# DM1090FFC_Connector.net
KiCad netlist of a schematic drawn in Altium Designer
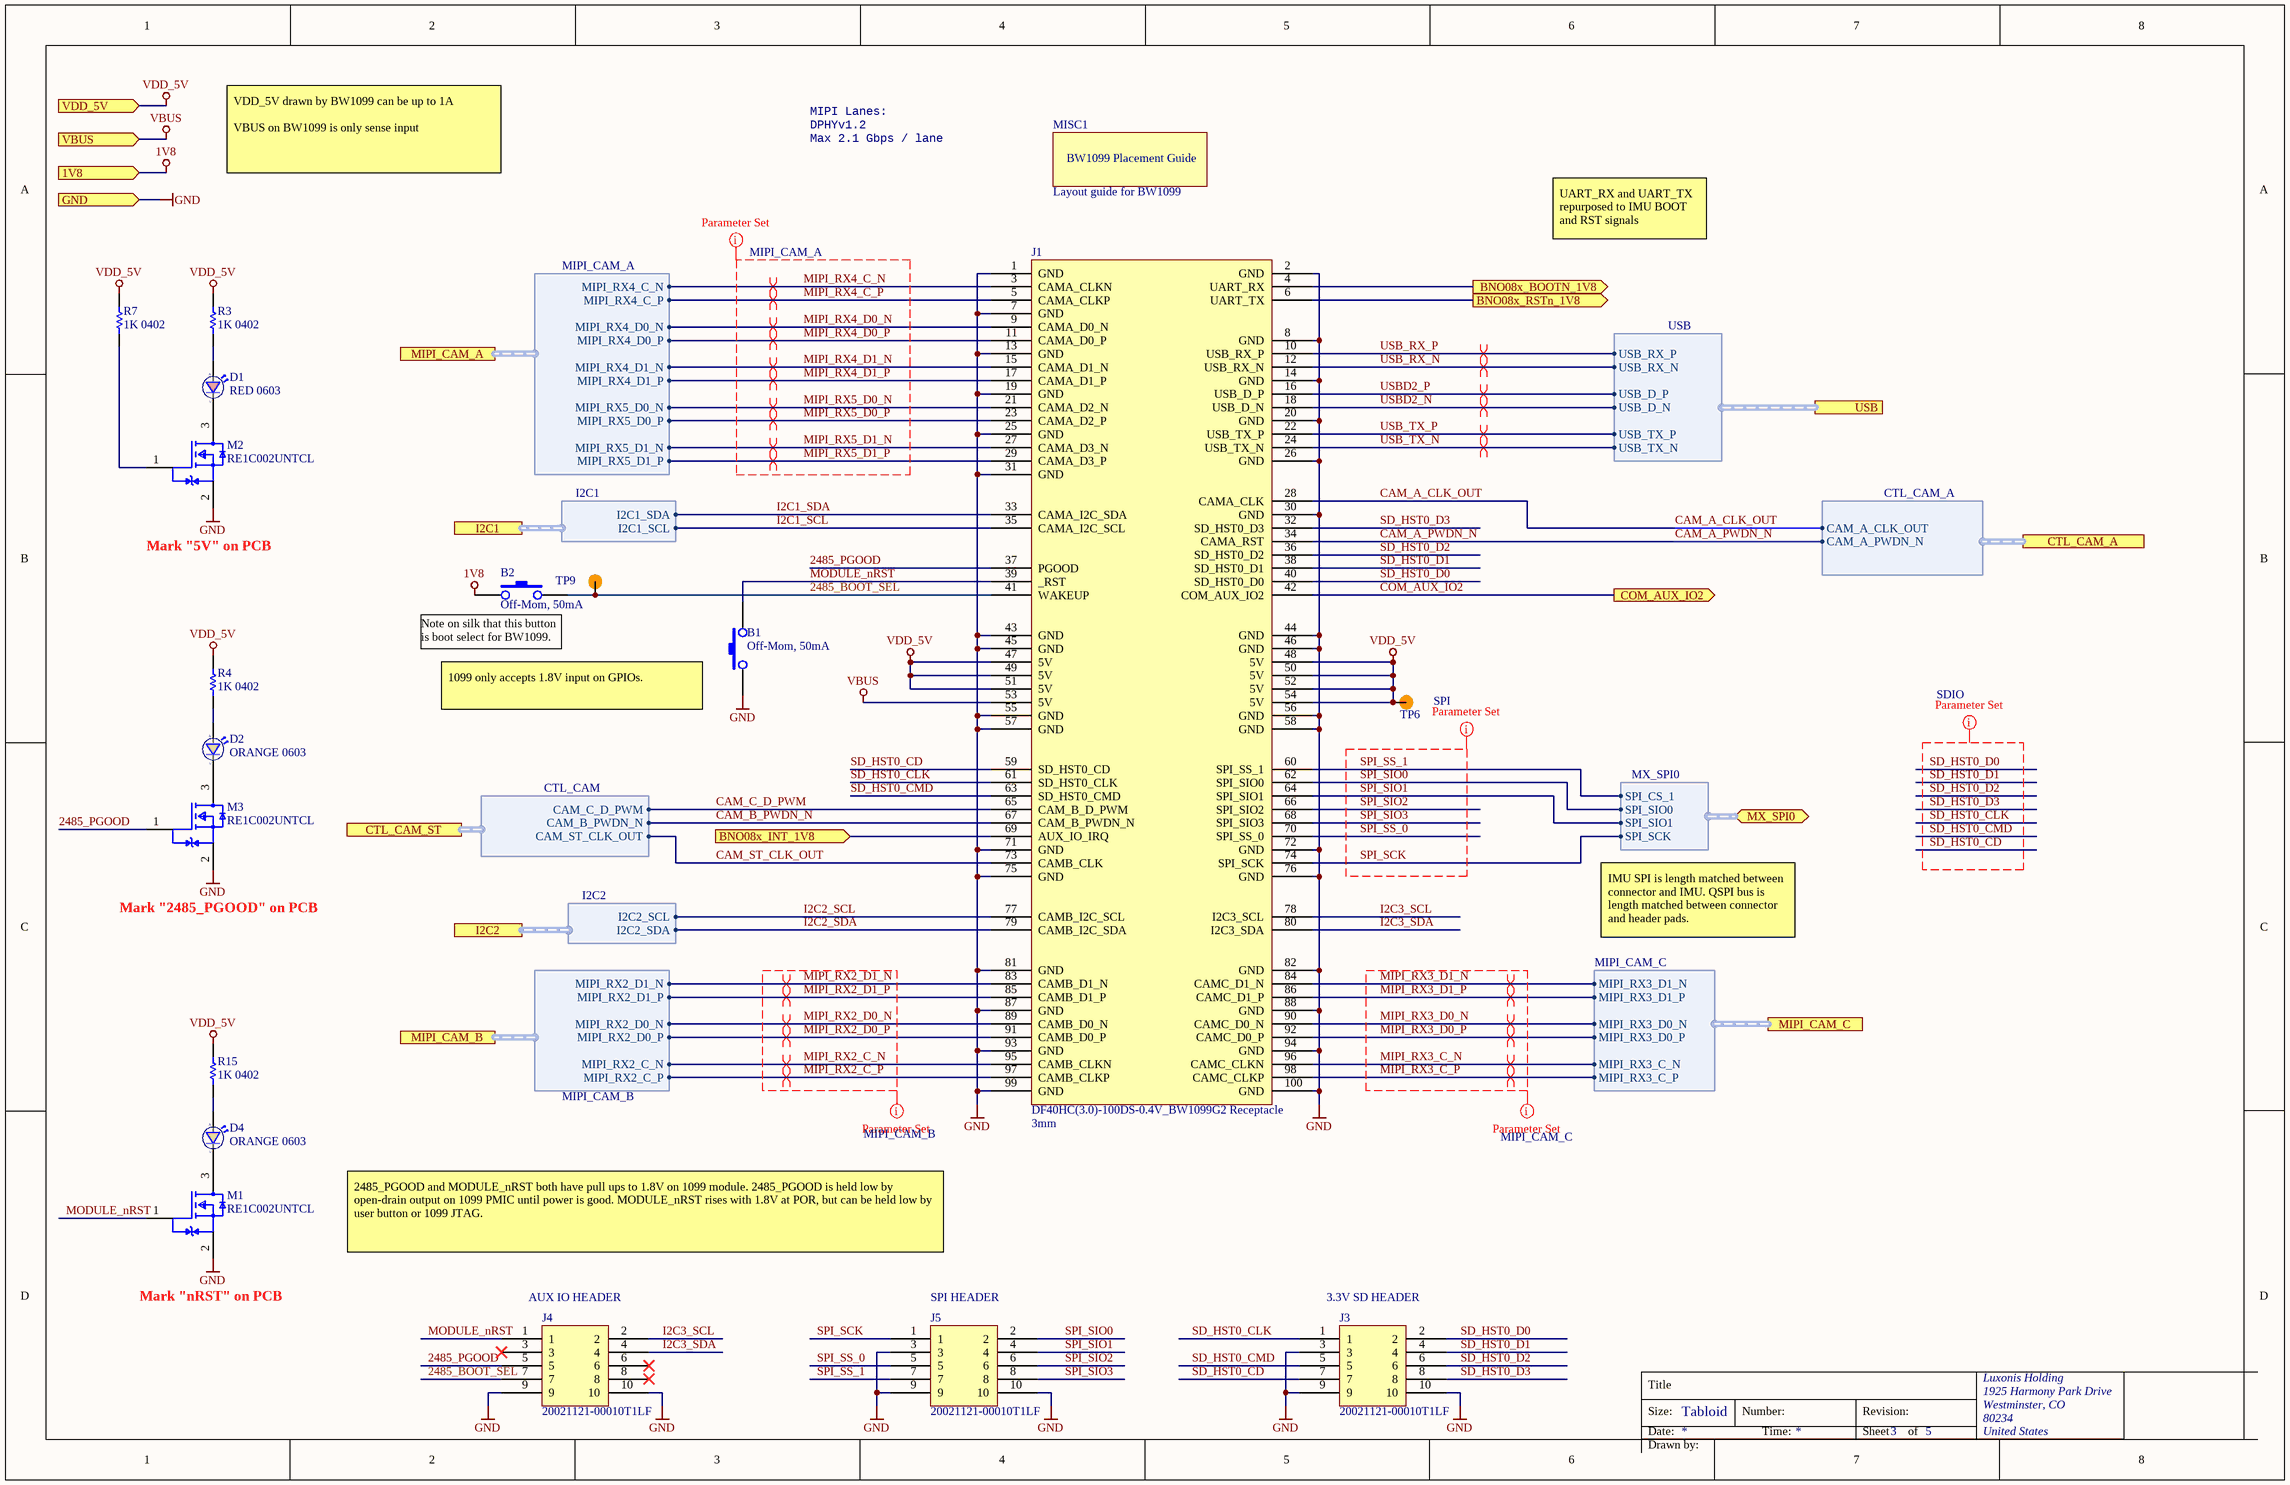
[diagram p0: DM1090FFC_Connector.SchDoc]

(export (version "E")
  (design (tool "Eeschema 10.0.6"))
  (components
    (comp (ref "B1")
      (value "Off-Mom, 50mA")
      (footprint "LuxonisMaster:DTSM-32N-V")
      (description "SWITCH TACTILE SMT 3.5mm * 6mm , brown 160gf")
      (libsource (lib "LuxonisMaster") (part "DTSM-32N-V"))
    )
    (comp (ref "B2")
      (value "Off-Mom, 50mA")
      (footprint "LuxonisMaster:DTSM-32N-V")
      (description "SWITCH TACTILE SMT 3.5mm * 6mm , brown 160gf")
      (libsource (lib "LuxonisMaster") (part "DTSM-32N-V"))
    )
    (comp (ref "D1")
      (value "RED 0603")
      (footprint "LuxonisMaster:SML_D1xx8W")
      (description "LED RED DIFFUSED 0603 SMD Red 620nm LED Indication - Discrete 2.2V 0603 (1608 Metric)")
      (libsource (lib "LuxonisMaster") (part "SML-D12U8WT86"))
    )
    (comp (ref "D2")
      (value "ORANGE 0603")
      (footprint "LuxonisMaster:SML_D1xx8W")
      (description "LED ORANGE DIFFUSED 0603 SMD Orange 605nm LED Indication - Discrete 2.2V 0603 (1608 Metric)")
      (libsource (lib "LuxonisMaster") (part "SML-D12D8WT86"))
    )
    (comp (ref "D4")
      (value "ORANGE 0603")
      (footprint "LuxonisMaster:SML_D1xx8W")
      (description "LED ORANGE DIFFUSED 0603 SMD Orange 605nm LED Indication - Discrete 2.2V 0603 (1608 Metric)")
      (libsource (lib "LuxonisMaster") (part "SML-D12D8WT86"))
    )
    (comp (ref "J1")
      (value "DF40HC(3.0)-100DS-0.4V_BW1099G2 Receptacle")
      (footprint "LuxonisMaster:DF40HC-3.0-100DS-0.4V_minpad")
      (description "CONN RCPT 100POS 0.4MM SMD GOLD")
      (fields (field (name "MATED STACKING HEIGHT") "3mm"))
      (libsource (lib "LuxonisMaster") (part "DF40HC(3.0)-100DS-0.4V_BW1099_G2"))
    )
    (comp (ref "J3")
      (value "20021121-00010T1LF")
      (footprint "LuxonisMaster:20021121-00010T1LF")
      (description "CONN HEADER SMD 10POS 1.27MM")
      (libsource (lib "LuxonisMaster") (part "20021121-00010T1LF"))
    )
    (comp (ref "J4")
      (value "20021121-00010T1LF")
      (footprint "LuxonisMaster:20021121-00010T1LF")
      (description "CONN HEADER SMD 10POS 1.27MM")
      (libsource (lib "LuxonisMaster") (part "20021121-00010T1LF"))
    )
    (comp (ref "J5")
      (value "20021121-00010T1LF")
      (footprint "LuxonisMaster:20021121-00010T1LF")
      (description "CONN HEADER SMD 10POS 1.27MM")
      (libsource (lib "LuxonisMaster") (part "20021121-00010T1LF"))
    )
    (comp (ref "M1")
      (value "RE1C002UNTCL")
      (footprint "LuxonisMaster:RE1C002UNTCL")
      (description "MOSFET N-CH 20V 0.2A EMT3")
      (libsource (lib "LuxonisMaster") (part "RE1C002UNTCL"))
    )
    (comp (ref "M2")
      (value "RE1C002UNTCL")
      (footprint "LuxonisMaster:RE1C002UNTCL")
      (description "MOSFET N-CH 20V 0.2A EMT3")
      (libsource (lib "LuxonisMaster") (part "RE1C002UNTCL"))
    )
    (comp (ref "M3")
      (value "RE1C002UNTCL")
      (footprint "LuxonisMaster:RE1C002UNTCL")
      (description "MOSFET N-CH 20V 0.2A EMT3")
      (libsource (lib "LuxonisMaster") (part "RE1C002UNTCL"))
    )
    (comp (ref "MISC1")
      (value "Layout guide for BW1099")
      (footprint "BW1099_R3_KTHSNF_Footprint")
      (description "MISC - Use for aligning BW1099 mount")
      (libsource (lib "LuxonisMaster") (part "BW1099_Footprint"))
    )
    (comp (ref "R3")
      (value "1K 0402")
      (footprint "RES_Altium_Vault_Generic:RESC0402(1005)_N")
      (fields (field (name "TOLERANCE") "1%"))
      (libsource (lib "LuxonisMaster") (part "RC0402FR-071KL"))
    )
    (comp (ref "R4")
      (value "1K 0402")
      (footprint "RES_Altium_Vault_Generic:RESC0402(1005)_N")
      (fields (field (name "TOLERANCE") "1%"))
      (libsource (lib "LuxonisMaster") (part "RC0402FR-071KL"))
    )
    (comp (ref "R7")
      (value "1K 0402")
      (footprint "RES_Altium_Vault_Generic:RESC0402(1005)_N")
      (fields (field (name "TOLERANCE") "1%"))
      (libsource (lib "LuxonisMaster") (part "RC0402FR-071KL"))
    )
    (comp (ref "R15")
      (value "1K 0402")
      (footprint "RES_Altium_Vault_Generic:RESC0402(1005)_N")
      (fields (field (name "TOLERANCE") "1%"))
      (libsource (lib "LuxonisMaster") (part "RC0402FR-071KL"))
    )
    (comp (ref "TP6")
      (value "TP100_200_NS")
      (footprint "LuxonisMaster:TP100_200_NS")
      (libsource (lib "LuxonisMaster") (part "TEST_POINT"))
    )
    (comp (ref "TP9")
      (value "TP100_200_NS")
      (footprint "LuxonisMaster:TP100_200_NS")
      (libsource (lib "LuxonisMaster") (part "TEST_POINT"))
    )
  )
  (nets
    (net (code "10") (name "/2485_BOOT_SEL") (class "Default")
      (node (ref "B2") (pin "2") (pinfunction "2_2") (pintype "passive"))
      (node (ref "J1") (pin "41") (pinfunction "WAKEUP_41") (pintype "passive"))
      (node (ref "J4") (pin "7") (pinfunction "7_7") (pintype "passive"))
      (node (ref "TP9") (pin "1") (pintype "passive"))
    )
    (net (code "11") (name "/2485_PGOOD") (class "Default")
      (node (ref "J1") (pin "37") (pinfunction "PGOOD_37") (pintype "passive"))
      (node (ref "J4") (pin "5") (pinfunction "5_5") (pintype "passive"))
      (node (ref "M3") (pin "1") (pinfunction "Gate_1") (pintype "passive"))
    )
    (net (code "12") (name "/BNO08x_BOOTN_1V8") (class "Default")
      (node (ref "J1") (pin "4") (pinfunction "UART_RX_4") (pintype "passive"))
    )
    (net (code "13") (name "/BNO08x_INT_1V8") (class "Default")
      (node (ref "J1") (pin "69") (pinfunction "AUX_IO_IRQ_69") (pintype "passive"))
    )
    (net (code "14") (name "/BNO08x_RSTn_1V8") (class "Default")
      (node (ref "J1") (pin "6") (pinfunction "UART_TX_6") (pintype "passive"))
    )
    (net (code "15") (name "/CAM_A_CLK_OUT") (class "Default")
      (node (ref "J1") (pin "28") (pinfunction "CAMA_CLK_28") (pintype "passive"))
    )
    (net (code "16") (name "/CAM_A_PWDN_N") (class "Default")
      (node (ref "J1") (pin "34") (pinfunction "CAMA_RST_34") (pintype "passive"))
    )
    (net (code "17") (name "/CAM_B_PWDN_N") (class "Default")
      (node (ref "J1") (pin "67") (pinfunction "CAM_B_PWDN_N_67") (pintype "passive"))
    )
    (net (code "18") (name "/CAM_C_D_PWM") (class "Default")
      (node (ref "J1") (pin "65") (pinfunction "CAM_B_D_PWM_65") (pintype "passive"))
    )
    (net (code "19") (name "/CAM_ST_CLK_OUT") (class "Default")
      (node (ref "J1") (pin "73") (pinfunction "CAMB_CLK_73") (pintype "passive"))
    )
    (net (code "20") (name "/COM_AUX_IO2") (class "Default")
      (node (ref "J1") (pin "42") (pinfunction "COM_AUX_IO2_42") (pintype "passive"))
    )
    (net (code "21") (name "/I2C1_SCL") (class "Default")
      (node (ref "J1") (pin "35") (pinfunction "CAMA_I2C_SCL_35") (pintype "passive"))
    )
    (net (code "22") (name "/I2C1_SDA") (class "Default")
      (node (ref "J1") (pin "33") (pinfunction "CAMA_I2C_SDA_33") (pintype "passive"))
    )
    (net (code "23") (name "/I2C2_SCL") (class "Default")
      (node (ref "J1") (pin "77") (pinfunction "CAMB_I2C_SCL_77") (pintype "passive"))
    )
    (net (code "24") (name "/I2C2_SDA") (class "Default")
      (node (ref "J1") (pin "79") (pinfunction "CAMB_I2C_SDA_79") (pintype "passive"))
    )
    (net (code "25") (name "/I2C3_SCL") (class "Default")
      (node (ref "J1") (pin "78") (pinfunction "I2C3_SCL_78") (pintype "passive"))
      (node (ref "J4") (pin "2") (pinfunction "2_2") (pintype "passive"))
    )
    (net (code "26") (name "/I2C3_SDA") (class "Default")
      (node (ref "J1") (pin "80") (pinfunction "I2C3_SDA_80") (pintype "passive"))
      (node (ref "J4") (pin "4") (pinfunction "4_4") (pintype "passive"))
    )
    (net (code "27") (name "/MIPI_RX2_C_N") (class "Default")
      (node (ref "J1") (pin "95") (pinfunction "CAMB_CLKN_95") (pintype "passive"))
    )
    (net (code "28") (name "/MIPI_RX2_C_P") (class "Default")
      (node (ref "J1") (pin "97") (pinfunction "CAMB_CLKP_97") (pintype "passive"))
    )
    (net (code "29") (name "/MIPI_RX2_D0_N") (class "Default")
      (node (ref "J1") (pin "89") (pinfunction "CAMB_D0_N_89") (pintype "passive"))
    )
    (net (code "30") (name "/MIPI_RX2_D0_P") (class "Default")
      (node (ref "J1") (pin "91") (pinfunction "CAMB_D0_P_91") (pintype "passive"))
    )
    (net (code "31") (name "/MIPI_RX2_D1_N") (class "Default")
      (node (ref "J1") (pin "83") (pinfunction "CAMB_D1_N_83") (pintype "passive"))
    )
    (net (code "32") (name "/MIPI_RX2_D1_P") (class "Default")
      (node (ref "J1") (pin "85") (pinfunction "CAMB_D1_P_85") (pintype "passive"))
    )
    (net (code "33") (name "/MIPI_RX3_C_N") (class "Default")
      (node (ref "J1") (pin "96") (pinfunction "CAMC_CLKN_96") (pintype "passive"))
    )
    (net (code "34") (name "/MIPI_RX3_C_P") (class "Default")
      (node (ref "J1") (pin "98") (pinfunction "CAMC_CLKP_98") (pintype "passive"))
    )
    (net (code "35") (name "/MIPI_RX3_D0_N") (class "Default")
      (node (ref "J1") (pin "90") (pinfunction "CAMC_D0_N_90") (pintype "passive"))
    )
    (net (code "36") (name "/MIPI_RX3_D0_P") (class "Default")
      (node (ref "J1") (pin "92") (pinfunction "CAMC_D0_P_92") (pintype "passive"))
    )
    (net (code "37") (name "/MIPI_RX3_D1_N") (class "Default")
      (node (ref "J1") (pin "84") (pinfunction "CAMC_D1_N_84") (pintype "passive"))
    )
    (net (code "38") (name "/MIPI_RX3_D1_P") (class "Default")
      (node (ref "J1") (pin "86") (pinfunction "CAMC_D1_P_86") (pintype "passive"))
    )
    (net (code "39") (name "/MIPI_RX4_C_N") (class "Default")
      (node (ref "J1") (pin "3") (pinfunction "CAMA_CLKN_3") (pintype "passive"))
    )
    (net (code "40") (name "/MIPI_RX4_C_P") (class "Default")
      (node (ref "J1") (pin "5") (pinfunction "CAMA_CLKP_5") (pintype "passive"))
    )
    (net (code "41") (name "/MIPI_RX4_D0_N") (class "Default")
      (node (ref "J1") (pin "9") (pinfunction "CAMA_D0_N_9") (pintype "passive"))
    )
    (net (code "42") (name "/MIPI_RX4_D0_P") (class "Default")
      (node (ref "J1") (pin "11") (pinfunction "CAMA_D0_P_11") (pintype "passive"))
    )
    (net (code "43") (name "/MIPI_RX4_D1_N") (class "Default")
      (node (ref "J1") (pin "15") (pinfunction "CAMA_D1_N_15") (pintype "passive"))
    )
    (net (code "44") (name "/MIPI_RX4_D1_P") (class "Default")
      (node (ref "J1") (pin "17") (pinfunction "CAMA_D1_P_17") (pintype "passive"))
    )
    (net (code "45") (name "/MIPI_RX5_D0_N") (class "Default")
      (node (ref "J1") (pin "21") (pinfunction "CAMA_D2_N_21") (pintype "passive"))
    )
    (net (code "46") (name "/MIPI_RX5_D0_P") (class "Default")
      (node (ref "J1") (pin "23") (pinfunction "CAMA_D2_P_23") (pintype "passive"))
    )
    (net (code "47") (name "/MIPI_RX5_D1_N") (class "Default")
      (node (ref "J1") (pin "27") (pinfunction "CAMA_D3_N_27") (pintype "passive"))
    )
    (net (code "48") (name "/MIPI_RX5_D1_P") (class "Default")
      (node (ref "J1") (pin "29") (pinfunction "CAMA_D3_P_29") (pintype "passive"))
    )
    (net (code "49") (name "/MODULE_nRST") (class "Default")
      (node (ref "B1") (pin "2") (pinfunction "2_2") (pintype "passive"))
      (node (ref "J1") (pin "39") (pinfunction "_RST_39") (pintype "passive"))
      (node (ref "J4") (pin "1") (pinfunction "1_1") (pintype "passive"))
      (node (ref "M1") (pin "1") (pinfunction "Gate_1") (pintype "passive"))
    )
    (net (code "50") (name "/SD_HST0_CD") (class "Default")
      (node (ref "J1") (pin "59") (pinfunction "SD_HST0_CD_59") (pintype "passive"))
      (node (ref "J3") (pin "7") (pinfunction "7_7") (pintype "passive"))
    )
    (net (code "51") (name "/SD_HST0_CLK") (class "Default")
      (node (ref "J1") (pin "61") (pinfunction "SD_HST0_CLK_61") (pintype "passive"))
      (node (ref "J3") (pin "1") (pinfunction "1_1") (pintype "passive"))
    )
    (net (code "52") (name "/SD_HST0_CMD") (class "Default")
      (node (ref "J1") (pin "63") (pinfunction "SD_HST0_CMD_63") (pintype "passive"))
      (node (ref "J3") (pin "5") (pinfunction "5_5") (pintype "passive"))
    )
    (net (code "53") (name "/SD_HST0_D0") (class "Default")
      (node (ref "J1") (pin "40") (pinfunction "SD_HST0_D0_40") (pintype "passive"))
      (node (ref "J3") (pin "2") (pinfunction "2_2") (pintype "passive"))
    )
    (net (code "54") (name "/SD_HST0_D1") (class "Default")
      (node (ref "J1") (pin "38") (pinfunction "SD_HST0_D1_38") (pintype "passive"))
      (node (ref "J3") (pin "4") (pinfunction "4_4") (pintype "passive"))
    )
    (net (code "55") (name "/SD_HST0_D2") (class "Default")
      (node (ref "J1") (pin "36") (pinfunction "SD_HST0_D2_36") (pintype "passive"))
      (node (ref "J3") (pin "6") (pinfunction "6_6") (pintype "passive"))
    )
    (net (code "56") (name "/SD_HST0_D3") (class "Default")
      (node (ref "J1") (pin "32") (pinfunction "SD_HST0_D3_32") (pintype "passive"))
      (node (ref "J3") (pin "8") (pinfunction "8_8") (pintype "passive"))
    )
    (net (code "57") (name "/SPI_SCK") (class "Default")
      (node (ref "J1") (pin "74") (pinfunction "SPI_SCK_74") (pintype "passive"))
      (node (ref "J5") (pin "1") (pinfunction "1_1") (pintype "passive"))
    )
    (net (code "58") (name "/SPI_SIO0") (class "Default")
      (node (ref "J1") (pin "62") (pinfunction "SPI_SIO0_62") (pintype "passive"))
      (node (ref "J5") (pin "2") (pinfunction "2_2") (pintype "passive"))
    )
    (net (code "59") (name "/SPI_SIO1") (class "Default")
      (node (ref "J1") (pin "64") (pinfunction "SPI_SIO1_64") (pintype "passive"))
      (node (ref "J5") (pin "4") (pinfunction "4_4") (pintype "passive"))
    )
    (net (code "60") (name "/SPI_SIO2") (class "Default")
      (node (ref "J1") (pin "66") (pinfunction "SPI_SIO2_66") (pintype "passive"))
      (node (ref "J5") (pin "6") (pinfunction "6_6") (pintype "passive"))
    )
    (net (code "61") (name "/SPI_SIO3") (class "Default")
      (node (ref "J1") (pin "68") (pinfunction "SPI_SIO3_68") (pintype "passive"))
      (node (ref "J5") (pin "8") (pinfunction "8_8") (pintype "passive"))
    )
    (net (code "62") (name "/SPI_SS_0") (class "Default")
      (node (ref "J1") (pin "70") (pinfunction "SPI_SS_0_70") (pintype "passive"))
      (node (ref "J5") (pin "5") (pinfunction "5_5") (pintype "passive"))
    )
    (net (code "63") (name "/SPI_SS_1") (class "Default")
      (node (ref "J1") (pin "60") (pinfunction "SPI_SS_1_60") (pintype "passive"))
      (node (ref "J5") (pin "7") (pinfunction "7_7") (pintype "passive"))
    )
    (net (code "64") (name "/USBD2_N") (class "Default")
      (node (ref "J1") (pin "18") (pinfunction "USB_D_N_18") (pintype "passive"))
    )
    (net (code "65") (name "/USBD2_P") (class "Default")
      (node (ref "J1") (pin "16") (pinfunction "USB_D_P_16") (pintype "passive"))
    )
    (net (code "66") (name "/USB_RX_N") (class "Default")
      (node (ref "J1") (pin "12") (pinfunction "USB_RX_N_12") (pintype "passive"))
    )
    (net (code "67") (name "/USB_RX_P") (class "Default")
      (node (ref "J1") (pin "10") (pinfunction "USB_RX_P_10") (pintype "passive"))
    )
    (net (code "68") (name "/USB_TX_N") (class "Default")
      (node (ref "J1") (pin "24") (pinfunction "USB_TX_N_24") (pintype "passive"))
    )
    (net (code "69") (name "/USB_TX_P") (class "Default")
      (node (ref "J1") (pin "22") (pinfunction "USB_TX_P_22") (pintype "passive"))
    )
    (net (code "79") (name "1V8") (class "Default")
      (node (ref "B2") (pin "1") (pinfunction "1_1") (pintype "passive"))
    )
    (net (code "80") (name "GND") (class "Default")
      (node (ref "B1") (pin "1") (pinfunction "1_1") (pintype "passive"))
      (node (ref "J1") (pin "1") (pinfunction "GND_1") (pintype "passive"))
      (node (ref "J1") (pin "100") (pinfunction "GND_100") (pintype "passive"))
      (node (ref "J1") (pin "13") (pinfunction "GND_13") (pintype "passive"))
      (node (ref "J1") (pin "14") (pinfunction "GND_14") (pintype "passive"))
      (node (ref "J1") (pin "19") (pinfunction "GND_19") (pintype "passive"))
      (node (ref "J1") (pin "2") (pinfunction "GND_2") (pintype "passive"))
      (node (ref "J1") (pin "20") (pinfunction "GND_20") (pintype "passive"))
      (node (ref "J1") (pin "25") (pinfunction "GND_25") (pintype "passive"))
      (node (ref "J1") (pin "26") (pinfunction "GND_26") (pintype "passive"))
      (node (ref "J1") (pin "30") (pinfunction "GND_30") (pintype "passive"))
      (node (ref "J1") (pin "31") (pinfunction "GND_31") (pintype "passive"))
      (node (ref "J1") (pin "43") (pinfunction "GND_43") (pintype "passive"))
      (node (ref "J1") (pin "44") (pinfunction "GND_44") (pintype "passive"))
      (node (ref "J1") (pin "45") (pinfunction "GND_45") (pintype "passive"))
      (node (ref "J1") (pin "46") (pinfunction "GND_46") (pintype "passive"))
      (node (ref "J1") (pin "55") (pinfunction "GND_55") (pintype "passive"))
      (node (ref "J1") (pin "56") (pinfunction "GND_56") (pintype "passive"))
      (node (ref "J1") (pin "57") (pinfunction "GND_57") (pintype "passive"))
      (node (ref "J1") (pin "58") (pinfunction "GND_58") (pintype "passive"))
      (node (ref "J1") (pin "7") (pinfunction "GND_7") (pintype "passive"))
      (node (ref "J1") (pin "71") (pinfunction "GND_71") (pintype "passive"))
      (node (ref "J1") (pin "72") (pinfunction "GND_72") (pintype "passive"))
      (node (ref "J1") (pin "75") (pinfunction "GND_75") (pintype "passive"))
      (node (ref "J1") (pin "76") (pinfunction "GND_76") (pintype "passive"))
      (node (ref "J1") (pin "8") (pinfunction "GND_8") (pintype "passive"))
      (node (ref "J1") (pin "81") (pinfunction "GND_81") (pintype "passive"))
      (node (ref "J1") (pin "82") (pinfunction "GND_82") (pintype "passive"))
      (node (ref "J1") (pin "87") (pinfunction "GND_87") (pintype "passive"))
      (node (ref "J1") (pin "88") (pinfunction "GND_88") (pintype "passive"))
      (node (ref "J1") (pin "93") (pinfunction "GND_93") (pintype "passive"))
      (node (ref "J1") (pin "94") (pinfunction "GND_94") (pintype "passive"))
      (node (ref "J1") (pin "99") (pinfunction "GND_99") (pintype "passive"))
      (node (ref "J3") (pin "10") (pinfunction "10_10") (pintype "passive"))
      (node (ref "J3") (pin "3") (pinfunction "3_3") (pintype "passive"))
      (node (ref "J3") (pin "9") (pinfunction "9_9") (pintype "passive"))
      (node (ref "J4") (pin "10") (pinfunction "10_10") (pintype "passive"))
      (node (ref "J4") (pin "9") (pinfunction "9_9") (pintype "passive"))
      (node (ref "J5") (pin "10") (pinfunction "10_10") (pintype "passive"))
      (node (ref "J5") (pin "3") (pinfunction "3_3") (pintype "passive"))
      (node (ref "J5") (pin "9") (pinfunction "9_9") (pintype "passive"))
      (node (ref "M1") (pin "2") (pinfunction "Source_2") (pintype "passive"))
      (node (ref "M2") (pin "2") (pinfunction "Source_2") (pintype "passive"))
      (node (ref "M3") (pin "2") (pinfunction "Source_2") (pintype "passive"))
    )
    (net (code "81") (name "Net-(D1-A)") (class "Default")
      (node (ref "D1") (pin "2") (pinfunction "A_2") (pintype "passive"))
      (node (ref "R3") (pin "1") (pinfunction "1_1") (pintype "passive"))
    )
    (net (code "82") (name "Net-(D1-C)") (class "Default")
      (node (ref "D1") (pin "1") (pinfunction "C_1") (pintype "passive"))
      (node (ref "M2") (pin "3") (pinfunction "Drain_3") (pintype "passive"))
    )
    (net (code "83") (name "Net-(D2-A)") (class "Default")
      (node (ref "D2") (pin "2") (pinfunction "A_2") (pintype "passive"))
      (node (ref "R4") (pin "1") (pinfunction "1_1") (pintype "passive"))
    )
    (net (code "84") (name "Net-(D2-C)") (class "Default")
      (node (ref "D2") (pin "1") (pinfunction "C_1") (pintype "passive"))
      (node (ref "M3") (pin "3") (pinfunction "Drain_3") (pintype "passive"))
    )
    (net (code "85") (name "Net-(D4-A)") (class "Default")
      (node (ref "D4") (pin "2") (pinfunction "A_2") (pintype "passive"))
      (node (ref "R15") (pin "1") (pinfunction "1_1") (pintype "passive"))
    )
    (net (code "86") (name "Net-(D4-C)") (class "Default")
      (node (ref "D4") (pin "1") (pinfunction "C_1") (pintype "passive"))
      (node (ref "M1") (pin "3") (pinfunction "Drain_3") (pintype "passive"))
    )
    (net (code "87") (name "Net-(M2-Gate)") (class "Default")
      (node (ref "M2") (pin "1") (pinfunction "Gate_1") (pintype "passive"))
      (node (ref "R7") (pin "1") (pinfunction "1_1") (pintype "passive"))
    )
    (net (code "88") (name "VBUS") (class "Default")
      (node (ref "J1") (pin "53") (pinfunction "5V_53") (pintype "passive"))
    )
    (net (code "89") (name "VDD_5V") (class "Default")
      (node (ref "J1") (pin "47") (pinfunction "5V_47") (pintype "passive"))
      (node (ref "J1") (pin "48") (pinfunction "5V_48") (pintype "passive"))
      (node (ref "J1") (pin "49") (pinfunction "5V_49") (pintype "passive"))
      (node (ref "J1") (pin "50") (pinfunction "5V_50") (pintype "passive"))
      (node (ref "J1") (pin "51") (pinfunction "5V_51") (pintype "passive"))
      (node (ref "J1") (pin "52") (pinfunction "5V_52") (pintype "passive"))
      (node (ref "J1") (pin "54") (pinfunction "5V_54") (pintype "passive"))
      (node (ref "R15") (pin "2") (pinfunction "2_2") (pintype "passive"))
      (node (ref "R3") (pin "2") (pinfunction "2_2") (pintype "passive"))
      (node (ref "R4") (pin "2") (pinfunction "2_2") (pintype "passive"))
      (node (ref "R7") (pin "2") (pinfunction "2_2") (pintype "passive"))
      (node (ref "TP6") (pin "1") (pintype "passive"))
    )
    (net (code "90") (name "unconnected-(J4-Pad3)") (class "Default")
      (node (ref "J4") (pin "3") (pinfunction "3_3") (pintype "passive+no_connect"))
    )
    (net (code "91") (name "unconnected-(J4-Pad6)") (class "Default")
      (node (ref "J4") (pin "6") (pinfunction "6_6") (pintype "passive+no_connect"))
    )
    (net (code "92") (name "unconnected-(J4-Pad8)") (class "Default")
      (node (ref "J4") (pin "8") (pinfunction "8_8") (pintype "passive+no_connect"))
    )
  )
)
